# MicroBit_Robot_Interface_RevB.net
KiCad netlist of a schematic drawn in EAGLE
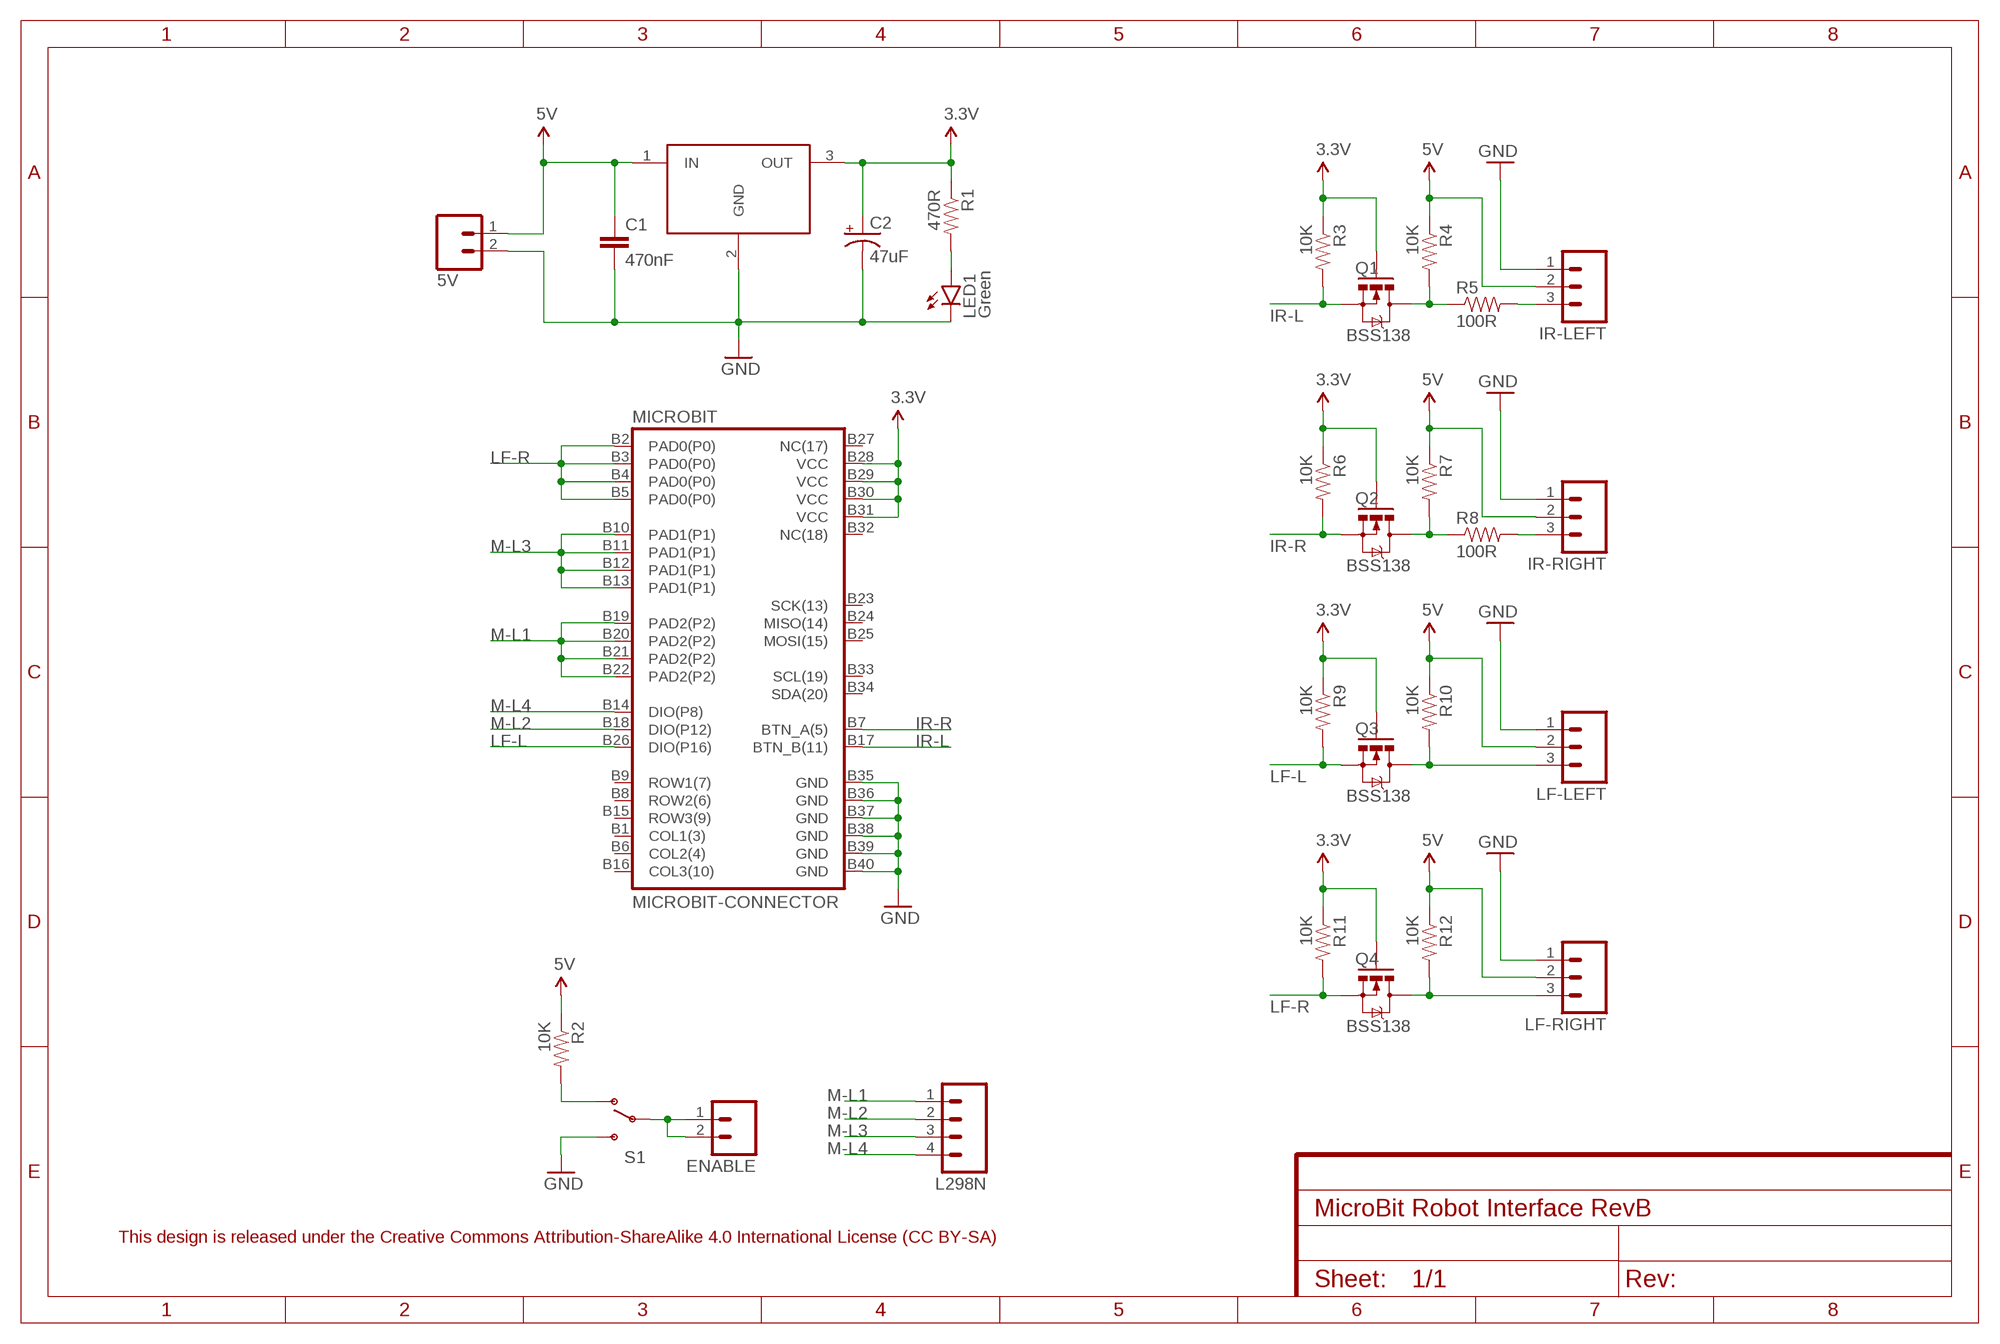
[diagram p0: schematic, sheet 1]

(export (version "E")
  (design (tool "Eeschema 10.0.6"))
  (components
    (comp (ref "5V")
      (value "MCOMP_SCREWTERM_2PIN5MM")
      (footprint "eagle-import:MCOMP-SCREWTERMINAL-5MM-2")
      (libsource (lib "eagle-import") (part "MCOMP_SCREWTERM_2PIN5MM"))
    )
    (comp (ref "C1")
      (value "470nF")
      (footprint "eagle-import:0603-CAP")
      (libsource (lib "eagle-import") (part "CAP0603-CAP"))
    )
    (comp (ref "C2")
      (value "47uF")
      (footprint "eagle-import:CPOL-RADIAL-100UF-25V")
      (libsource (lib "eagle-import") (part "CAP_POLPTH1"))
    )
    (comp (ref "ENABLE")
      (value "M02PTH")
      (footprint "eagle-import:1X02")
      (libsource (lib "eagle-import") (part "M02PTH"))
    )
    (comp (ref "IR-LEFT")
      (value "M03PTH")
      (footprint "eagle-import:1X03")
      (libsource (lib "eagle-import") (part "M03PTH"))
    )
    (comp (ref "IR-RIGHT")
      (value "M03PTH")
      (footprint "eagle-import:1X03")
      (libsource (lib "eagle-import") (part "M03PTH"))
    )
    (comp (ref "L298N")
      (value "M04PTH")
      (footprint "eagle-import:1X04")
      (libsource (lib "eagle-import") (part "M04PTH"))
    )
    (comp (ref "LED1")
      (value "Green")
      (footprint "eagle-import:LED3MM")
      (libsource (lib "eagle-import") (part "LED3MM"))
    )
    (comp (ref "LF-LEFT")
      (value "M03PTH")
      (footprint "eagle-import:1X03")
      (libsource (lib "eagle-import") (part "M03PTH"))
    )
    (comp (ref "LF-RIGHT")
      (value "M03PTH")
      (footprint "eagle-import:1X03")
      (libsource (lib "eagle-import") (part "M03PTH"))
    )
    (comp (ref "MICROBIT")
      (value "MICROBIT-CONNECTOR")
      (footprint "eagle-import:RBB40DHHN_MICROBIT")
      (libsource (lib "eagle-import") (part "MICROBIT-CONNECTOR"))
    )
    (comp (ref "Q1")
      (value "BSS138")
      (footprint "eagle-import:SOT23-3")
      (libsource (lib "eagle-import") (part "MOSFET-NCHANNELBSS138"))
    )
    (comp (ref "Q2")
      (value "BSS138")
      (footprint "eagle-import:SOT23-3")
      (libsource (lib "eagle-import") (part "MOSFET-NCHANNELBSS138"))
    )
    (comp (ref "Q3")
      (value "BSS138")
      (footprint "eagle-import:SOT23-3")
      (libsource (lib "eagle-import") (part "MOSFET-NCHANNELBSS138"))
    )
    (comp (ref "Q4")
      (value "BSS138")
      (footprint "eagle-import:SOT23-3")
      (libsource (lib "eagle-import") (part "MOSFET-NCHANNELBSS138"))
    )
    (comp (ref "R1")
      (value "470R")
      (footprint "eagle-import:0603-RES")
      (libsource (lib "eagle-import") (part "RESISTOR0603-RES"))
    )
    (comp (ref "R2")
      (value "10K")
      (footprint "eagle-import:0603-RES")
      (libsource (lib "eagle-import") (part "RESISTOR0603-RES"))
    )
    (comp (ref "R3")
      (value "10K")
      (footprint "eagle-import:0603-RES")
      (libsource (lib "eagle-import") (part "RESISTOR0603-RES"))
    )
    (comp (ref "R4")
      (value "10K")
      (footprint "eagle-import:0603-RES")
      (libsource (lib "eagle-import") (part "RESISTOR0603-RES"))
    )
    (comp (ref "R5")
      (value "100R")
      (footprint "eagle-import:0603-RES")
      (libsource (lib "eagle-import") (part "RESISTOR0603-RES"))
    )
    (comp (ref "R6")
      (value "10K")
      (footprint "eagle-import:0603-RES")
      (libsource (lib "eagle-import") (part "RESISTOR0603-RES"))
    )
    (comp (ref "R7")
      (value "10K")
      (footprint "eagle-import:0603-RES")
      (libsource (lib "eagle-import") (part "RESISTOR0603-RES"))
    )
    (comp (ref "R8")
      (value "100R")
      (footprint "eagle-import:0603-RES")
      (libsource (lib "eagle-import") (part "RESISTOR0603-RES"))
    )
    (comp (ref "R9")
      (value "10K")
      (footprint "eagle-import:0603-RES")
      (libsource (lib "eagle-import") (part "RESISTOR0603-RES"))
    )
    (comp (ref "R10")
      (value "10K")
      (footprint "eagle-import:0603-RES")
      (libsource (lib "eagle-import") (part "RESISTOR0603-RES"))
    )
    (comp (ref "R11")
      (value "10K")
      (footprint "eagle-import:0603-RES")
      (libsource (lib "eagle-import") (part "RESISTOR0603-RES"))
    )
    (comp (ref "R12")
      (value "10K")
      (footprint "eagle-import:0603-RES")
      (libsource (lib "eagle-import") (part "RESISTOR0603-RES"))
    )
    (comp (ref "S1")
      (value "KNITTER-SWITCH-MFP106D")
      (footprint "eagle-import:KNITTER-SWITCH-MFP106D")
      (libsource (lib "eagle-import") (part "KNITTER-SWITCH-MFP106D"))
    )
    (comp (ref "VR1")
      (value "LM3940IMP-3.3")
      (footprint "eagle-import:SOT223")
      (libsource (lib "eagle-import") (part "LM3940IMP-3.3"))
    )
  )
  (nets
    (net (code "1") (name "/IR-L") (class "Default")
      (node (ref "MICROBIT") (pin "B17") (pinfunction "BTN_B(11)_B17") (pintype "input"))
      (node (ref "Q1") (pin "2") (pinfunction "S_2") (pintype "passive"))
      (node (ref "R3") (pin "2") (pinfunction "2_2") (pintype "passive"))
    )
    (net (code "2") (name "/IR-R") (class "Default")
      (node (ref "MICROBIT") (pin "B7") (pinfunction "BTN_A(5)_B7") (pintype "input"))
      (node (ref "Q2") (pin "2") (pinfunction "S_2") (pintype "passive"))
      (node (ref "R6") (pin "2") (pinfunction "2_2") (pintype "passive"))
    )
    (net (code "3") (name "/LF-L") (class "Default")
      (node (ref "MICROBIT") (pin "B26") (pinfunction "DIO(P16)_B26") (pintype "bidirectional"))
      (node (ref "Q3") (pin "2") (pinfunction "S_2") (pintype "passive"))
      (node (ref "R9") (pin "2") (pinfunction "2_2") (pintype "passive"))
    )
    (net (code "4") (name "/LF-R") (class "Default")
      (node (ref "MICROBIT") (pin "B2") (pinfunction "PAD0(P0)_B2") (pintype "bidirectional"))
      (node (ref "MICROBIT") (pin "B3") (pinfunction "PAD0(P0)_B3") (pintype "bidirectional"))
      (node (ref "MICROBIT") (pin "B4") (pinfunction "PAD0(P0)_B4") (pintype "bidirectional"))
      (node (ref "MICROBIT") (pin "B5") (pinfunction "PAD0(P0)_B5") (pintype "bidirectional"))
      (node (ref "Q4") (pin "2") (pinfunction "S_2") (pintype "passive"))
      (node (ref "R11") (pin "2") (pinfunction "2_2") (pintype "passive"))
    )
    (net (code "5") (name "/M-L1") (class "Default")
      (node (ref "L298N") (pin "1") (pinfunction "1_1") (pintype "passive"))
      (node (ref "MICROBIT") (pin "B19") (pinfunction "PAD2(P2)_B19") (pintype "bidirectional"))
      (node (ref "MICROBIT") (pin "B20") (pinfunction "PAD2(P2)_B20") (pintype "bidirectional"))
      (node (ref "MICROBIT") (pin "B21") (pinfunction "PAD2(P2)_B21") (pintype "bidirectional"))
      (node (ref "MICROBIT") (pin "B22") (pinfunction "PAD2(P2)_B22") (pintype "bidirectional"))
    )
    (net (code "6") (name "/M-L2") (class "Default")
      (node (ref "L298N") (pin "2") (pinfunction "2_2") (pintype "passive"))
      (node (ref "MICROBIT") (pin "B18") (pinfunction "DIO(P12)_B18") (pintype "bidirectional"))
    )
    (net (code "7") (name "/M-L3") (class "Default")
      (node (ref "L298N") (pin "3") (pinfunction "3_3") (pintype "passive"))
      (node (ref "MICROBIT") (pin "B10") (pinfunction "PAD1(P1)_B10") (pintype "bidirectional"))
      (node (ref "MICROBIT") (pin "B11") (pinfunction "PAD1(P1)_B11") (pintype "bidirectional"))
      (node (ref "MICROBIT") (pin "B12") (pinfunction "PAD1(P1)_B12") (pintype "bidirectional"))
      (node (ref "MICROBIT") (pin "B13") (pinfunction "PAD1(P1)_B13") (pintype "bidirectional"))
    )
    (net (code "8") (name "/M-L4") (class "Default")
      (node (ref "L298N") (pin "4") (pinfunction "4_4") (pintype "passive"))
      (node (ref "MICROBIT") (pin "B14") (pinfunction "DIO(P8)_B14") (pintype "bidirectional"))
    )
    (net (code "9") (name "3.3V") (class "Default")
      (node (ref "C2") (pin "1") (pinfunction "+_1") (pintype "passive"))
      (node (ref "MICROBIT") (pin "B28") (pinfunction "VCC_B28") (pintype "power_in"))
      (node (ref "MICROBIT") (pin "B29") (pinfunction "VCC_B29") (pintype "power_in"))
      (node (ref "MICROBIT") (pin "B30") (pinfunction "VCC_B30") (pintype "power_in"))
      (node (ref "MICROBIT") (pin "B31") (pinfunction "VCC_B31") (pintype "power_in"))
      (node (ref "Q1") (pin "1") (pinfunction "G_1") (pintype "passive"))
      (node (ref "Q2") (pin "1") (pinfunction "G_1") (pintype "passive"))
      (node (ref "Q3") (pin "1") (pinfunction "G_1") (pintype "passive"))
      (node (ref "Q4") (pin "1") (pinfunction "G_1") (pintype "passive"))
      (node (ref "R1") (pin "1") (pinfunction "1_1") (pintype "passive"))
      (node (ref "R11") (pin "1") (pinfunction "1_1") (pintype "passive"))
      (node (ref "R3") (pin "1") (pinfunction "1_1") (pintype "passive"))
      (node (ref "R6") (pin "1") (pinfunction "1_1") (pintype "passive"))
      (node (ref "R9") (pin "1") (pinfunction "1_1") (pintype "passive"))
      (node (ref "VR1") (pin "3") (pinfunction "OUT_3") (pintype "power_in"))
    )
    (net (code "10") (name "5V") (class "Default")
      (node (ref "5V") (pin "1") (pinfunction "1_1") (pintype "passive"))
      (node (ref "C1") (pin "1") (pinfunction "1_1") (pintype "passive"))
      (node (ref "IR-LEFT") (pin "2") (pinfunction "2_2") (pintype "passive"))
      (node (ref "IR-RIGHT") (pin "2") (pinfunction "2_2") (pintype "passive"))
      (node (ref "LF-LEFT") (pin "2") (pinfunction "2_2") (pintype "passive"))
      (node (ref "LF-RIGHT") (pin "2") (pinfunction "2_2") (pintype "passive"))
      (node (ref "R10") (pin "1") (pinfunction "1_1") (pintype "passive"))
      (node (ref "R12") (pin "1") (pinfunction "1_1") (pintype "passive"))
      (node (ref "R2") (pin "1") (pinfunction "1_1") (pintype "passive"))
      (node (ref "R4") (pin "1") (pinfunction "1_1") (pintype "passive"))
      (node (ref "R7") (pin "1") (pinfunction "1_1") (pintype "passive"))
      (node (ref "VR1") (pin "1") (pinfunction "IN_1") (pintype "power_in"))
    )
    (net (code "11") (name "GND") (class "Default")
      (node (ref "5V") (pin "2") (pinfunction "2_2") (pintype "passive"))
      (node (ref "C1") (pin "2") (pinfunction "2_2") (pintype "passive"))
      (node (ref "C2") (pin "2") (pinfunction "-_2") (pintype "passive"))
      (node (ref "IR-LEFT") (pin "1") (pinfunction "1_1") (pintype "passive"))
      (node (ref "IR-RIGHT") (pin "1") (pinfunction "1_1") (pintype "passive"))
      (node (ref "LED1") (pin "K") (pinfunction "C_K") (pintype "passive"))
      (node (ref "LF-LEFT") (pin "1") (pinfunction "1_1") (pintype "passive"))
      (node (ref "LF-RIGHT") (pin "1") (pinfunction "1_1") (pintype "passive"))
      (node (ref "MICROBIT") (pin "B35") (pinfunction "GND_B35") (pintype "power_in"))
      (node (ref "MICROBIT") (pin "B36") (pinfunction "GND_B36") (pintype "power_in"))
      (node (ref "MICROBIT") (pin "B37") (pinfunction "GND_B37") (pintype "power_in"))
      (node (ref "MICROBIT") (pin "B38") (pinfunction "GND_B38") (pintype "power_in"))
      (node (ref "MICROBIT") (pin "B39") (pinfunction "GND_B39") (pintype "power_in"))
      (node (ref "MICROBIT") (pin "B40") (pinfunction "GND_B40") (pintype "power_in"))
      (node (ref "S1") (pin "P$2") (pinfunction "POS2_P$2") (pintype "passive"))
      (node (ref "VR1") (pin "2") (pinfunction "GND_2") (pintype "power_in"))
    )
    (net (code "12") (name "Net-(IR-LEFT-Pad3)") (class "Default")
      (node (ref "IR-LEFT") (pin "3") (pinfunction "3_3") (pintype "passive"))
      (node (ref "R5") (pin "2") (pinfunction "2_2") (pintype "passive"))
    )
    (net (code "13") (name "Net-(IR-RIGHT-Pad3)") (class "Default")
      (node (ref "IR-RIGHT") (pin "3") (pinfunction "3_3") (pintype "passive"))
      (node (ref "R8") (pin "2") (pinfunction "2_2") (pintype "passive"))
    )
    (net (code "14") (name "Net-(LED1-PadA)") (class "Default")
      (node (ref "LED1") (pin "A") (pinfunction "A_A") (pintype "passive"))
      (node (ref "R1") (pin "2") (pinfunction "2_2") (pintype "passive"))
    )
    (net (code "15") (name "Net-(Q1-D)") (class "Default")
      (node (ref "Q1") (pin "3") (pinfunction "D_3") (pintype "passive"))
      (node (ref "R4") (pin "2") (pinfunction "2_2") (pintype "passive"))
      (node (ref "R5") (pin "1") (pinfunction "1_1") (pintype "passive"))
    )
    (net (code "16") (name "Net-(Q2-D)") (class "Default")
      (node (ref "Q2") (pin "3") (pinfunction "D_3") (pintype "passive"))
      (node (ref "R7") (pin "2") (pinfunction "2_2") (pintype "passive"))
      (node (ref "R8") (pin "1") (pinfunction "1_1") (pintype "passive"))
    )
    (net (code "17") (name "Net-(Q3-D)") (class "Default")
      (node (ref "LF-LEFT") (pin "3") (pinfunction "3_3") (pintype "passive"))
      (node (ref "Q3") (pin "3") (pinfunction "D_3") (pintype "passive"))
      (node (ref "R10") (pin "2") (pinfunction "2_2") (pintype "passive"))
    )
    (net (code "18") (name "Net-(Q4-D)") (class "Default")
      (node (ref "LF-RIGHT") (pin "3") (pinfunction "3_3") (pintype "passive"))
      (node (ref "Q4") (pin "3") (pinfunction "D_3") (pintype "passive"))
      (node (ref "R12") (pin "2") (pinfunction "2_2") (pintype "passive"))
    )
    (net (code "19") (name "Net-(S1-COMMON)") (class "Default")
      (node (ref "ENABLE") (pin "1") (pinfunction "1_1") (pintype "passive"))
      (node (ref "ENABLE") (pin "2") (pinfunction "2_2") (pintype "passive"))
      (node (ref "S1") (pin "WIPER") (pinfunction "COMMON_WIPER") (pintype "passive"))
    )
    (net (code "20") (name "Net-(S1-POS1)") (class "Default")
      (node (ref "R2") (pin "2") (pinfunction "2_2") (pintype "passive"))
      (node (ref "S1") (pin "P$1") (pinfunction "POS1_P$1") (pintype "passive"))
    )
    (net (code "21") (name "unconnected-(MICROBIT-COL1(3)-PadB1)") (class "Default")
      (node (ref "MICROBIT") (pin "B1") (pinfunction "COL1(3)_B1") (pintype "output"))
    )
    (net (code "22") (name "unconnected-(MICROBIT-COL2(4)-PadB6)") (class "Default")
      (node (ref "MICROBIT") (pin "B6") (pinfunction "COL2(4)_B6") (pintype "output"))
    )
    (net (code "23") (name "unconnected-(MICROBIT-COL3(10)-PadB16)") (class "Default")
      (node (ref "MICROBIT") (pin "B16") (pinfunction "COL3(10)_B16") (pintype "output"))
    )
    (net (code "24") (name "unconnected-(MICROBIT-MISO(14)-PadB24)") (class "Default")
      (node (ref "MICROBIT") (pin "B24") (pinfunction "MISO(14)_B24") (pintype "bidirectional"))
    )
    (net (code "25") (name "unconnected-(MICROBIT-MOSI(15)-PadB25)") (class "Default")
      (node (ref "MICROBIT") (pin "B25") (pinfunction "MOSI(15)_B25") (pintype "bidirectional"))
    )
    (net (code "26") (name "unconnected-(MICROBIT-NC(17)-PadB27)") (class "Default")
      (node (ref "MICROBIT") (pin "B27") (pinfunction "NC(17)_B27") (pintype "no_connect"))
    )
    (net (code "27") (name "unconnected-(MICROBIT-NC(18)-PadB32)") (class "Default")
      (node (ref "MICROBIT") (pin "B32") (pinfunction "NC(18)_B32") (pintype "no_connect"))
    )
    (net (code "28") (name "unconnected-(MICROBIT-ROW1(7)-PadB9)") (class "Default")
      (node (ref "MICROBIT") (pin "B9") (pinfunction "ROW1(7)_B9") (pintype "output"))
    )
    (net (code "29") (name "unconnected-(MICROBIT-ROW2(6)-PadB8)") (class "Default")
      (node (ref "MICROBIT") (pin "B8") (pinfunction "ROW2(6)_B8") (pintype "output"))
    )
    (net (code "30") (name "unconnected-(MICROBIT-ROW3(9)-PadB15)") (class "Default")
      (node (ref "MICROBIT") (pin "B15") (pinfunction "ROW3(9)_B15") (pintype "output"))
    )
    (net (code "31") (name "unconnected-(MICROBIT-SCK(13)-PadB23)") (class "Default")
      (node (ref "MICROBIT") (pin "B23") (pinfunction "SCK(13)_B23") (pintype "bidirectional"))
    )
    (net (code "32") (name "unconnected-(MICROBIT-SCL(19)-PadB33)") (class "Default")
      (node (ref "MICROBIT") (pin "B33") (pinfunction "SCL(19)_B33") (pintype "bidirectional"))
    )
    (net (code "33") (name "unconnected-(MICROBIT-SDA(20)-PadB34)") (class "Default")
      (node (ref "MICROBIT") (pin "B34") (pinfunction "SDA(20)_B34") (pintype "bidirectional"))
    )
  )
)
